# tactileSensorI2c.net
KiCad netlist of a schematic drawn in EAGLE
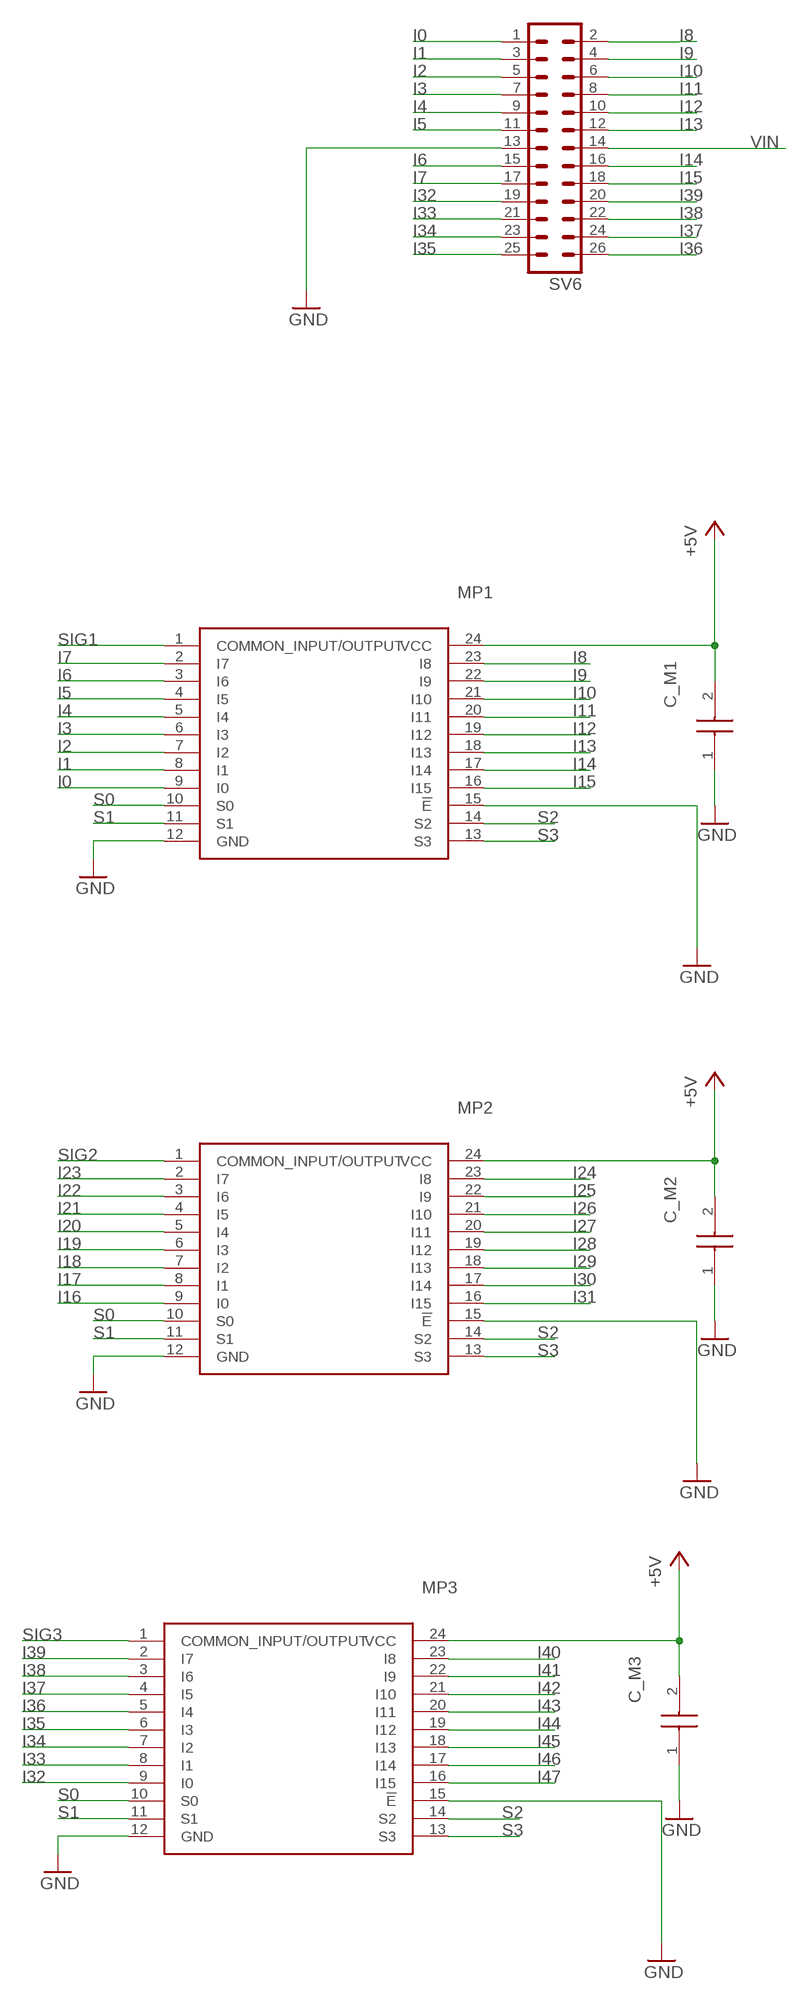
[diagram p0: schematic, sheet 1, part 1 of 2]
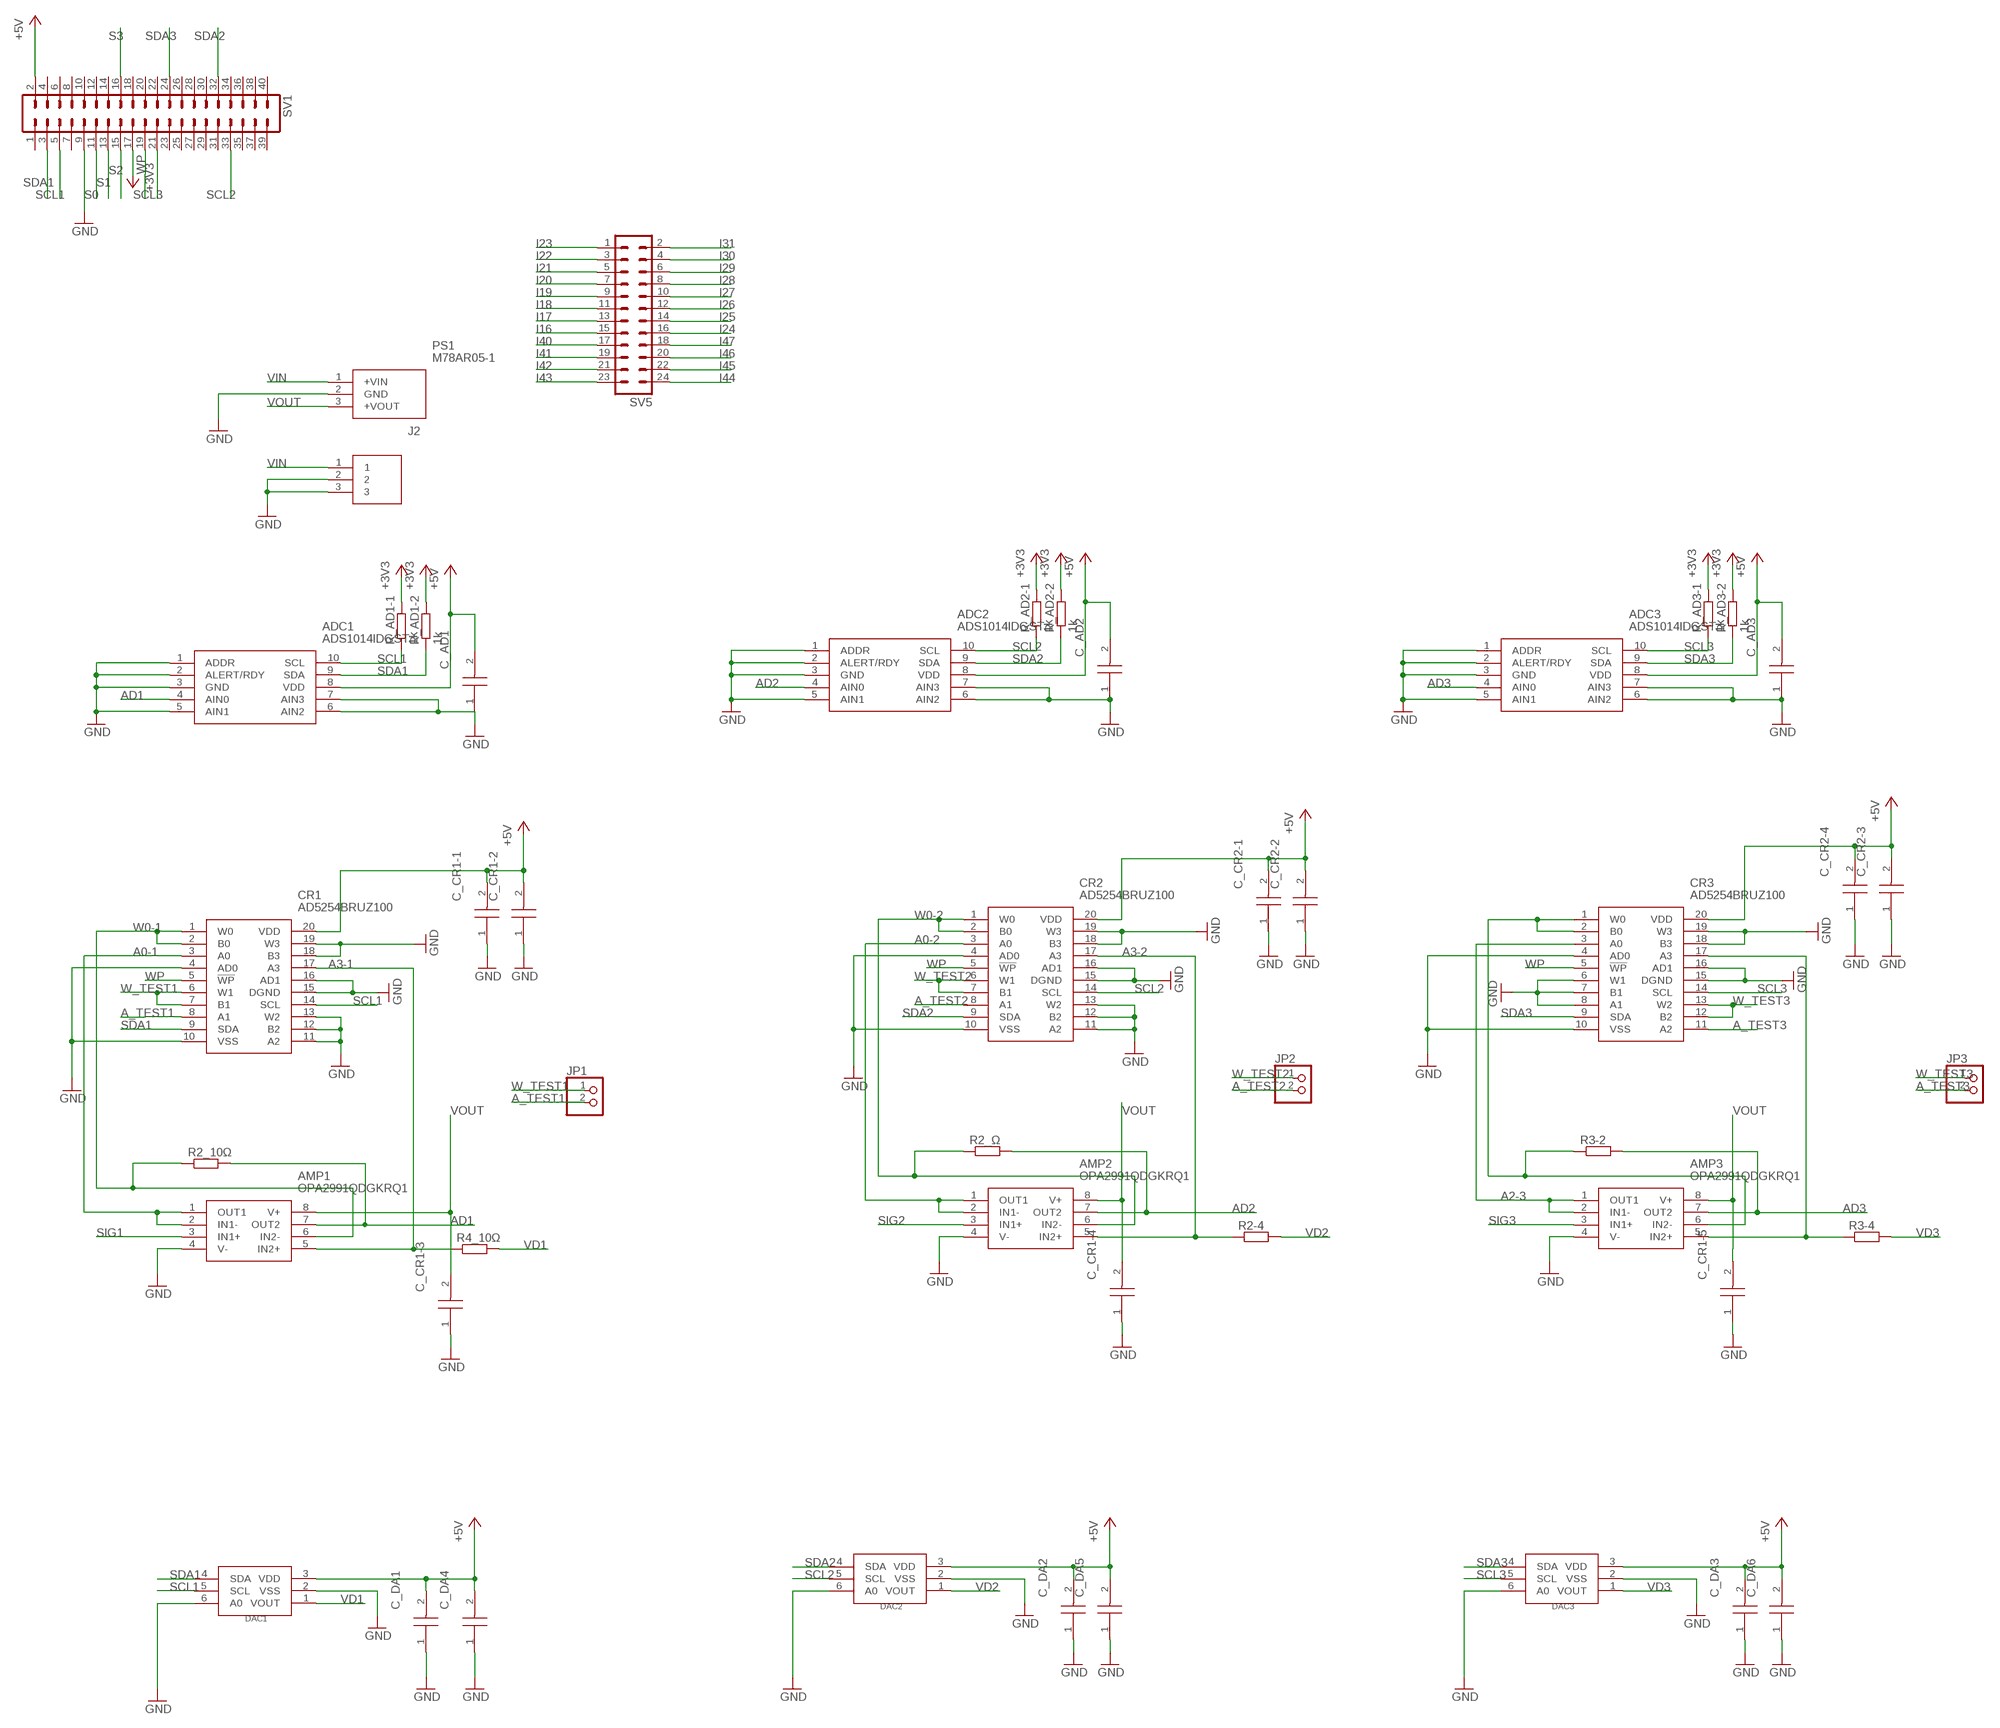
[diagram p1: schematic, sheet 1, part 2 of 2]

(export (version "E")
  (design (tool "Eeschema 10.0.6"))
  (components
    (comp (ref "ADC1")
      (value "ADS1014IDGST")
      (footprint "eagle-import:SOP50P490X110-10N")
      (fields (field (name "RS_PART_NUMBER") "7094557P"))
      (libsource (lib "eagle-import") (part "ADS1014IDGST"))
    )
    (comp (ref "ADC2")
      (value "ADS1014IDGST")
      (footprint "eagle-import:SOP50P490X110-10N")
      (fields (field (name "RS_PART_NUMBER") "7094557P"))
      (libsource (lib "eagle-import") (part "ADS1014IDGST"))
    )
    (comp (ref "ADC3")
      (value "ADS1014IDGST")
      (footprint "eagle-import:SOP50P490X110-10N")
      (fields (field (name "RS_PART_NUMBER") "7094557P"))
      (libsource (lib "eagle-import") (part "ADS1014IDGST"))
    )
    (comp (ref "AMP1")
      (value "OPA2991QDGKRQ1")
      (footprint "eagle-import:SOP65P490X110-8N")
      (libsource (lib "eagle-import") (part "OPA2991QDGKRQ1"))
    )
    (comp (ref "AMP2")
      (value "OPA2991QDGKRQ1")
      (footprint "eagle-import:SOP65P490X110-8N")
      (libsource (lib "eagle-import") (part "OPA2991QDGKRQ1"))
    )
    (comp (ref "AMP3")
      (value "OPA2991QDGKRQ1")
      (footprint "eagle-import:SOP65P490X110-8N")
      (libsource (lib "eagle-import") (part "OPA2991QDGKRQ1"))
    )
    (comp (ref "CR1")
      (value "AD5254BRUZ100")
      (footprint "eagle-import:SOP65P640X120-20N")
      (fields (field (name "RS_PART_NUMBER") "5384858P"))
      (libsource (lib "eagle-import") (part "AD5254BRUZ100"))
    )
    (comp (ref "CR2")
      (value "AD5254BRUZ100")
      (footprint "eagle-import:SOP65P640X120-20N")
      (fields (field (name "RS_PART_NUMBER") "5384858P"))
      (libsource (lib "eagle-import") (part "AD5254BRUZ100"))
    )
    (comp (ref "CR3")
      (value "AD5254BRUZ100")
      (footprint "eagle-import:SOP65P640X120-20N")
      (fields (field (name "RS_PART_NUMBER") "5384858P"))
      (libsource (lib "eagle-import") (part "AD5254BRUZ100"))
    )
    (comp (ref "C_AD1")
      (value "0.1u")
      (footprint "eagle-import:CAPC2012X140N")
      (fields
        (field (name "MANUFACTURER_PART_NUMBER") "C0805C105J3RACTU")
        (field (name "RS_PART_NUMBER") "1464275P")
      )
      (libsource (lib "eagle-import") (part "C0805C105J3RACTU"))
    )
    (comp (ref "C_AD2")
      (value "0.1u")
      (footprint "eagle-import:CAPC2012X140N")
      (fields
        (field (name "MANUFACTURER_PART_NUMBER") "C0805C105J3RACTU")
        (field (name "RS_PART_NUMBER") "1464275P")
      )
      (libsource (lib "eagle-import") (part "C0805C105J3RACTU"))
    )
    (comp (ref "C_AD3")
      (value "0.1u")
      (footprint "eagle-import:CAPC2012X140N")
      (fields
        (field (name "MANUFACTURER_PART_NUMBER") "C0805C105J3RACTU")
        (field (name "RS_PART_NUMBER") "1464275P")
      )
      (libsource (lib "eagle-import") (part "C0805C105J3RACTU"))
    )
    (comp (ref "C_CR1-1")
      (value "0.1u")
      (footprint "eagle-import:CAPC2012X140N")
      (fields
        (field (name "MANUFACTURER_PART_NUMBER") "C0805C105J3RACTU")
        (field (name "RS_PART_NUMBER") "1464275P")
      )
      (libsource (lib "eagle-import") (part "C0805C105J3RACTU"))
    )
    (comp (ref "C_CR1-2")
      (value "10u")
      (footprint "eagle-import:CAPC2012X140N")
      (fields
        (field (name "MANUFACTURER_PART_NUMBER") "C0805C105J3RACTU")
        (field (name "RS_PART_NUMBER") "1464275P")
      )
      (libsource (lib "eagle-import") (part "C0805C105J3RACTU"))
    )
    (comp (ref "C_CR1-3")
      (value "10u")
      (footprint "eagle-import:CAPC2012X140N")
      (fields
        (field (name "MANUFACTURER_PART_NUMBER") "C0805C105J3RACTU")
        (field (name "RS_PART_NUMBER") "1464275P")
      )
      (libsource (lib "eagle-import") (part "C0805C105J3RACTU"))
    )
    (comp (ref "C_CR1-4")
      (value "10u")
      (footprint "eagle-import:CAPC2012X140N")
      (fields
        (field (name "MANUFACTURER_PART_NUMBER") "C0805C105J3RACTU")
        (field (name "RS_PART_NUMBER") "1464275P")
      )
      (libsource (lib "eagle-import") (part "C0805C105J3RACTU"))
    )
    (comp (ref "C_CR1-5")
      (value "10u")
      (footprint "eagle-import:CAPC2012X140N")
      (fields
        (field (name "MANUFACTURER_PART_NUMBER") "C0805C105J3RACTU")
        (field (name "RS_PART_NUMBER") "1464275P")
      )
      (libsource (lib "eagle-import") (part "C0805C105J3RACTU"))
    )
    (comp (ref "C_CR2-1")
      (value "0.1u")
      (footprint "eagle-import:CAPC2012X140N")
      (fields
        (field (name "MANUFACTURER_PART_NUMBER") "C0805C105J3RACTU")
        (field (name "RS_PART_NUMBER") "1464275P")
      )
      (libsource (lib "eagle-import") (part "C0805C105J3RACTU"))
    )
    (comp (ref "C_CR2-2")
      (value "10u")
      (footprint "eagle-import:CAPC2012X140N")
      (fields
        (field (name "MANUFACTURER_PART_NUMBER") "C0805C105J3RACTU")
        (field (name "RS_PART_NUMBER") "1464275P")
      )
      (libsource (lib "eagle-import") (part "C0805C105J3RACTU"))
    )
    (comp (ref "C_CR2-3")
      (value "C0805C105J3RACTU")
      (footprint "eagle-import:CAPC2012X140N")
      (fields (field (name "RS_PART_NUMBER") "1464275P"))
      (libsource (lib "eagle-import") (part "C0805C105J3RACTU"))
    )
    (comp (ref "C_CR2-4")
      (value "C0805C105J3RACTU")
      (footprint "eagle-import:CAPC2012X140N")
      (fields (field (name "RS_PART_NUMBER") "1464275P"))
      (libsource (lib "eagle-import") (part "C0805C105J3RACTU"))
    )
    (comp (ref "C_DA1")
      (value "C0805C105J3RACTU")
      (footprint "eagle-import:CAPC2012X140N")
      (fields (field (name "RS_PART_NUMBER") "1464275P"))
      (libsource (lib "eagle-import") (part "C0805C105J3RACTU"))
    )
    (comp (ref "C_DA2")
      (value "C0805C105J3RACTU")
      (footprint "eagle-import:CAPC2012X140N")
      (fields (field (name "RS_PART_NUMBER") "1464275P"))
      (libsource (lib "eagle-import") (part "C0805C105J3RACTU"))
    )
    (comp (ref "C_DA3")
      (value "C0805C105J3RACTU")
      (footprint "eagle-import:CAPC2012X140N")
      (fields (field (name "RS_PART_NUMBER") "1464275P"))
      (libsource (lib "eagle-import") (part "C0805C105J3RACTU"))
    )
    (comp (ref "C_DA4")
      (value "C0805C105J3RACTU")
      (footprint "eagle-import:CAPC2012X140N")
      (fields (field (name "RS_PART_NUMBER") "1464275P"))
      (libsource (lib "eagle-import") (part "C0805C105J3RACTU"))
    )
    (comp (ref "C_DA5")
      (value "C0805C105J3RACTU")
      (footprint "eagle-import:CAPC2012X140N")
      (fields (field (name "RS_PART_NUMBER") "1464275P"))
      (libsource (lib "eagle-import") (part "C0805C105J3RACTU"))
    )
    (comp (ref "C_DA6")
      (value "C0805C105J3RACTU")
      (footprint "eagle-import:CAPC2012X140N")
      (fields (field (name "RS_PART_NUMBER") "1464275P"))
      (libsource (lib "eagle-import") (part "C0805C105J3RACTU"))
    )
    (comp (ref "C_M1")
      (value "0.1u")
      (footprint "eagle-import:CAPC2012X140N")
      (fields
        (field (name "MANUFACTURER_PART_NUMBER") "C0805C105J3RACTU")
        (field (name "RS_PART_NUMBER") "1464275P")
      )
      (libsource (lib "eagle-import") (part "C0805C105J3RACTU"))
    )
    (comp (ref "C_M2")
      (value "0.1u")
      (footprint "eagle-import:CAPC2012X140N")
      (fields
        (field (name "MANUFACTURER_PART_NUMBER") "C0805C105J3RACTU")
        (field (name "RS_PART_NUMBER") "1464275P")
      )
      (libsource (lib "eagle-import") (part "C0805C105J3RACTU"))
    )
    (comp (ref "C_M3")
      (value "0.1u")
      (footprint "eagle-import:CAPC2012X140N")
      (fields
        (field (name "MANUFACTURER_PART_NUMBER") "C0805C105J3RACTU")
        (field (name "RS_PART_NUMBER") "1464275P")
      )
      (libsource (lib "eagle-import") (part "C0805C105J3RACTU"))
    )
    (comp (ref "DAC1")
      (value "MCP4725")
      (footprint "eagle-import:SOT23-6")
      (libsource (lib "eagle-import") (part "MCP4725"))
    )
    (comp (ref "DAC2")
      (value "MCP4725")
      (footprint "eagle-import:SOT23-6")
      (libsource (lib "eagle-import") (part "MCP4725"))
    )
    (comp (ref "DAC3")
      (value "MCP4725")
      (footprint "eagle-import:SOT23-6")
      (libsource (lib "eagle-import") (part "MCP4725"))
    )
    (comp (ref "J2")
      (value "1725669")
      (footprint "eagle-import:1725669")
      (fields (field (name "MOUSER_PART_NUMBER") "651-1725669"))
      (libsource (lib "eagle-import") (part "1725669"))
    )
    (comp (ref "JP1")
      (value "PINHD-1X2")
      (footprint "eagle-import:1X02")
      (libsource (lib "eagle-import") (part "PINHD-1X2"))
    )
    (comp (ref "JP2")
      (value "PINHD-1X2")
      (footprint "eagle-import:1X02")
      (libsource (lib "eagle-import") (part "PINHD-1X2"))
    )
    (comp (ref "JP3")
      (value "PINHD-1X2")
      (footprint "eagle-import:1X02")
      (libsource (lib "eagle-import") (part "PINHD-1X2"))
    )
    (comp (ref "MP1")
      (value "CD74HC4067SM96")
      (footprint "eagle-import:SOP65P780X200-24N")
      (fields (field (name "MOUSER_PART_NUMBER") "595-CD74HC4067SM96"))
      (libsource (lib "eagle-import") (part "CD74HC4067SM96"))
    )
    (comp (ref "MP2")
      (value "CD74HC4067SM96")
      (footprint "eagle-import:SOP65P780X200-24N")
      (fields (field (name "MOUSER_PART_NUMBER") "595-CD74HC4067SM96"))
      (libsource (lib "eagle-import") (part "CD74HC4067SM96"))
    )
    (comp (ref "MP3")
      (value "CD74HC4067SM96")
      (footprint "eagle-import:SOP65P780X200-24N")
      (fields (field (name "MOUSER_PART_NUMBER") "595-CD74HC4067SM96"))
      (libsource (lib "eagle-import") (part "CD74HC4067SM96"))
    )
    (comp (ref "PS1")
      (value "M78AR05-1")
      (footprint "eagle-import:M78AR05")
      (libsource (lib "eagle-import") (part "M78AR05-1"))
    )
    (comp (ref "R2-4")
      (value "R-EU_0204/2V")
      (footprint "eagle-import:0204V")
      (libsource (lib "eagle-import") (part "R-EU_0204/2V"))
    )
    (comp (ref "R2_10Ω")
      (value "R-EU_0204/2V")
      (footprint "eagle-import:0204V")
      (libsource (lib "eagle-import") (part "R-EU_0204/2V"))
    )
    (comp (ref "R2_Ω")
      (value "R-EU_0204/2V")
      (footprint "eagle-import:0204V")
      (libsource (lib "eagle-import") (part "R-EU_0204/2V"))
    )
    (comp (ref "R3-2")
      (value "R-EU_0204/2V")
      (footprint "eagle-import:0204V")
      (libsource (lib "eagle-import") (part "R-EU_0204/2V"))
    )
    (comp (ref "R3-4")
      (value "R-EU_0204/2V")
      (footprint "eagle-import:0204V")
      (libsource (lib "eagle-import") (part "R-EU_0204/2V"))
    )
    (comp (ref "R4_10Ω")
      (value "R-EU_0204/2V")
      (footprint "eagle-import:0204V")
      (libsource (lib "eagle-import") (part "R-EU_0204/2V"))
    )
    (comp (ref "R_AD1-1")
      (value "1k")
      (footprint "eagle-import:R0805")
      (libsource (lib "eagle-import") (part "R-EU_R0805"))
    )
    (comp (ref "R_AD1-2")
      (value "1k")
      (footprint "eagle-import:R0805")
      (libsource (lib "eagle-import") (part "R-EU_R0805"))
    )
    (comp (ref "R_AD2-1")
      (value "1k")
      (footprint "eagle-import:R0805")
      (libsource (lib "eagle-import") (part "R-EU_R0805"))
    )
    (comp (ref "R_AD2-2")
      (value "1k")
      (footprint "eagle-import:R0805")
      (libsource (lib "eagle-import") (part "R-EU_R0805"))
    )
    (comp (ref "R_AD3-1")
      (value "1k")
      (footprint "eagle-import:R0805")
      (libsource (lib "eagle-import") (part "R-EU_R0805"))
    )
    (comp (ref "R_AD3-2")
      (value "1k")
      (footprint "eagle-import:R0805")
      (libsource (lib "eagle-import") (part "R-EU_R0805"))
    )
    (comp (ref "SV1")
      (value "MA20-2")
      (footprint "eagle-import:MA20-2")
      (libsource (lib "eagle-import") (part "MA20-2"))
    )
    (comp (ref "SV5")
      (value "MA12-2")
      (footprint "eagle-import:MA12-2")
      (libsource (lib "eagle-import") (part "MA12-2"))
    )
    (comp (ref "SV6")
      (value "MA13-2")
      (footprint "eagle-import:MA13-2")
      (libsource (lib "eagle-import") (part "MA13-2"))
    )
  )
  (nets
    (net (code "1") (name "+3V3") (class "Default")
      (node (ref "R_AD1-1") (pin "2") (pinfunction "2_2") (pintype "passive"))
      (node (ref "R_AD1-2") (pin "2") (pinfunction "2_2") (pintype "passive"))
      (node (ref "R_AD2-1") (pin "2") (pinfunction "2_2") (pintype "passive"))
      (node (ref "R_AD2-2") (pin "2") (pinfunction "2_2") (pintype "passive"))
      (node (ref "R_AD3-1") (pin "2") (pinfunction "2_2") (pintype "passive"))
      (node (ref "R_AD3-2") (pin "2") (pinfunction "2_2") (pintype "passive"))
      (node (ref "SV1") (pin "17") (pinfunction "17_17") (pintype "passive"))
    )
    (net (code "2") (name "+5V") (class "Default")
      (node (ref "ADC1") (pin "8") (pinfunction "VDD_8") (pintype "bidirectional"))
      (node (ref "ADC2") (pin "8") (pinfunction "VDD_8") (pintype "bidirectional"))
      (node (ref "ADC3") (pin "8") (pinfunction "VDD_8") (pintype "bidirectional"))
      (node (ref "CR1") (pin "20") (pinfunction "VDD_20") (pintype "bidirectional"))
      (node (ref "CR2") (pin "20") (pinfunction "VDD_20") (pintype "bidirectional"))
      (node (ref "CR3") (pin "20") (pinfunction "VDD_20") (pintype "bidirectional"))
      (node (ref "C_AD1") (pin "2") (pinfunction "2_2") (pintype "bidirectional"))
      (node (ref "C_AD2") (pin "2") (pinfunction "2_2") (pintype "bidirectional"))
      (node (ref "C_AD3") (pin "2") (pinfunction "2_2") (pintype "bidirectional"))
      (node (ref "C_CR1-1") (pin "2") (pinfunction "2_2") (pintype "bidirectional"))
      (node (ref "C_CR1-2") (pin "2") (pinfunction "2_2") (pintype "bidirectional"))
      (node (ref "C_CR2-1") (pin "2") (pinfunction "2_2") (pintype "bidirectional"))
      (node (ref "C_CR2-2") (pin "2") (pinfunction "2_2") (pintype "bidirectional"))
      (node (ref "C_CR2-3") (pin "2") (pinfunction "2_2") (pintype "bidirectional"))
      (node (ref "C_CR2-4") (pin "2") (pinfunction "2_2") (pintype "bidirectional"))
      (node (ref "C_DA1") (pin "2") (pinfunction "2_2") (pintype "bidirectional"))
      (node (ref "C_DA2") (pin "2") (pinfunction "2_2") (pintype "bidirectional"))
      (node (ref "C_DA3") (pin "2") (pinfunction "2_2") (pintype "bidirectional"))
      (node (ref "C_DA4") (pin "2") (pinfunction "2_2") (pintype "bidirectional"))
      (node (ref "C_DA5") (pin "2") (pinfunction "2_2") (pintype "bidirectional"))
      (node (ref "C_DA6") (pin "2") (pinfunction "2_2") (pintype "bidirectional"))
      (node (ref "C_M1") (pin "2") (pinfunction "2_2") (pintype "bidirectional"))
      (node (ref "C_M2") (pin "2") (pinfunction "2_2") (pintype "bidirectional"))
      (node (ref "C_M3") (pin "2") (pinfunction "2_2") (pintype "bidirectional"))
      (node (ref "DAC1") (pin "3") (pinfunction "VDD_3") (pintype "bidirectional"))
      (node (ref "DAC2") (pin "3") (pinfunction "VDD_3") (pintype "bidirectional"))
      (node (ref "DAC3") (pin "3") (pinfunction "VDD_3") (pintype "bidirectional"))
      (node (ref "MP1") (pin "24") (pinfunction "VCC_24") (pintype "bidirectional"))
      (node (ref "MP2") (pin "24") (pinfunction "VCC_24") (pintype "bidirectional"))
      (node (ref "MP3") (pin "24") (pinfunction "VCC_24") (pintype "bidirectional"))
      (node (ref "SV1") (pin "2") (pinfunction "2_2") (pintype "passive"))
    )
    (net (code "3") (name "/A0-1") (class "Default")
      (node (ref "AMP1") (pin "1") (pinfunction "OUT1_1") (pintype "bidirectional"))
      (node (ref "AMP1") (pin "2") (pinfunction "IN1-_2") (pintype "bidirectional"))
      (node (ref "CR1") (pin "3") (pinfunction "A0_3") (pintype "bidirectional"))
    )
    (net (code "4") (name "/A0-2") (class "Default")
      (node (ref "AMP2") (pin "1") (pinfunction "OUT1_1") (pintype "bidirectional"))
      (node (ref "AMP2") (pin "2") (pinfunction "IN1-_2") (pintype "bidirectional"))
      (node (ref "CR2") (pin "3") (pinfunction "A0_3") (pintype "bidirectional"))
    )
    (net (code "5") (name "/A2-3") (class "Default")
      (node (ref "AMP3") (pin "1") (pinfunction "OUT1_1") (pintype "bidirectional"))
      (node (ref "AMP3") (pin "2") (pinfunction "IN1-_2") (pintype "bidirectional"))
      (node (ref "CR3") (pin "3") (pinfunction "A0_3") (pintype "bidirectional"))
    )
    (net (code "6") (name "/A3-1") (class "Default")
      (node (ref "AMP1") (pin "5") (pinfunction "IN2+_5") (pintype "bidirectional"))
      (node (ref "CR1") (pin "17") (pinfunction "A3_17") (pintype "bidirectional"))
      (node (ref "R4_10Ω") (pin "1") (pinfunction "1_1") (pintype "passive"))
    )
    (net (code "7") (name "/A3-2") (class "Default")
      (node (ref "AMP2") (pin "5") (pinfunction "IN2+_5") (pintype "bidirectional"))
      (node (ref "CR2") (pin "17") (pinfunction "A3_17") (pintype "bidirectional"))
      (node (ref "R2-4") (pin "1") (pinfunction "1_1") (pintype "passive"))
    )
    (net (code "8") (name "/AD1") (class "Default")
      (node (ref "ADC1") (pin "4") (pinfunction "AIN0_4") (pintype "bidirectional"))
      (node (ref "AMP1") (pin "7") (pinfunction "OUT2_7") (pintype "bidirectional"))
      (node (ref "R2_10Ω") (pin "2") (pinfunction "2_2") (pintype "passive"))
    )
    (net (code "9") (name "/AD2") (class "Default")
      (node (ref "ADC2") (pin "4") (pinfunction "AIN0_4") (pintype "bidirectional"))
      (node (ref "AMP2") (pin "7") (pinfunction "OUT2_7") (pintype "bidirectional"))
      (node (ref "R2_Ω") (pin "2") (pinfunction "2_2") (pintype "passive"))
    )
    (net (code "10") (name "/AD3") (class "Default")
      (node (ref "ADC3") (pin "4") (pinfunction "AIN0_4") (pintype "bidirectional"))
      (node (ref "AMP3") (pin "7") (pinfunction "OUT2_7") (pintype "bidirectional"))
      (node (ref "R3-2") (pin "2") (pinfunction "2_2") (pintype "passive"))
    )
    (net (code "11") (name "/A_TEST1") (class "Default")
      (node (ref "CR1") (pin "8") (pinfunction "A1_8") (pintype "bidirectional"))
      (node (ref "JP1") (pin "2") (pinfunction "2_2") (pintype "passive"))
    )
    (net (code "12") (name "/A_TEST2") (class "Default")
      (node (ref "CR2") (pin "8") (pinfunction "A1_8") (pintype "bidirectional"))
      (node (ref "JP2") (pin "2") (pinfunction "2_2") (pintype "passive"))
    )
    (net (code "13") (name "/A_TEST3") (class "Default")
      (node (ref "CR3") (pin "11") (pinfunction "A2_11") (pintype "bidirectional"))
      (node (ref "JP3") (pin "2") (pinfunction "2_2") (pintype "passive"))
    )
    (net (code "14") (name "/I0") (class "Default")
      (node (ref "MP1") (pin "9") (pinfunction "I0_9") (pintype "bidirectional"))
      (node (ref "SV6") (pin "1") (pinfunction "1_1") (pintype "passive"))
    )
    (net (code "15") (name "/I1") (class "Default")
      (node (ref "MP1") (pin "8") (pinfunction "I1_8") (pintype "bidirectional"))
      (node (ref "SV6") (pin "3") (pinfunction "3_3") (pintype "passive"))
    )
    (net (code "16") (name "/I2") (class "Default")
      (node (ref "MP1") (pin "7") (pinfunction "I2_7") (pintype "bidirectional"))
      (node (ref "SV6") (pin "5") (pinfunction "5_5") (pintype "passive"))
    )
    (net (code "17") (name "/I3") (class "Default")
      (node (ref "MP1") (pin "6") (pinfunction "I3_6") (pintype "bidirectional"))
      (node (ref "SV6") (pin "7") (pinfunction "7_7") (pintype "passive"))
    )
    (net (code "18") (name "/I4") (class "Default")
      (node (ref "MP1") (pin "5") (pinfunction "I4_5") (pintype "bidirectional"))
      (node (ref "SV6") (pin "9") (pinfunction "9_9") (pintype "passive"))
    )
    (net (code "19") (name "/I5") (class "Default")
      (node (ref "MP1") (pin "4") (pinfunction "I5_4") (pintype "bidirectional"))
      (node (ref "SV6") (pin "11") (pinfunction "11_11") (pintype "passive"))
    )
    (net (code "20") (name "/I6") (class "Default")
      (node (ref "MP1") (pin "3") (pinfunction "I6_3") (pintype "bidirectional"))
      (node (ref "SV6") (pin "15") (pinfunction "15_15") (pintype "passive"))
    )
    (net (code "21") (name "/I7") (class "Default")
      (node (ref "MP1") (pin "2") (pinfunction "I7_2") (pintype "bidirectional"))
      (node (ref "SV6") (pin "17") (pinfunction "17_17") (pintype "passive"))
    )
    (net (code "22") (name "/I8") (class "Default")
      (node (ref "MP1") (pin "23") (pinfunction "I8_23") (pintype "bidirectional"))
      (node (ref "SV6") (pin "2") (pinfunction "2_2") (pintype "passive"))
    )
    (net (code "23") (name "/I9") (class "Default")
      (node (ref "MP1") (pin "22") (pinfunction "I9_22") (pintype "bidirectional"))
      (node (ref "SV6") (pin "4") (pinfunction "4_4") (pintype "passive"))
    )
    (net (code "24") (name "/I10") (class "Default")
      (node (ref "MP1") (pin "21") (pinfunction "I10_21") (pintype "bidirectional"))
      (node (ref "SV6") (pin "6") (pinfunction "6_6") (pintype "passive"))
    )
    (net (code "25") (name "/I11") (class "Default")
      (node (ref "MP1") (pin "20") (pinfunction "I11_20") (pintype "bidirectional"))
      (node (ref "SV6") (pin "8") (pinfunction "8_8") (pintype "passive"))
    )
    (net (code "26") (name "/I12") (class "Default")
      (node (ref "MP1") (pin "19") (pinfunction "I12_19") (pintype "bidirectional"))
      (node (ref "SV6") (pin "10") (pinfunction "10_10") (pintype "passive"))
    )
    (net (code "27") (name "/I13") (class "Default")
      (node (ref "MP1") (pin "18") (pinfunction "I13_18") (pintype "bidirectional"))
      (node (ref "SV6") (pin "12") (pinfunction "12_12") (pintype "passive"))
    )
    (net (code "28") (name "/I14") (class "Default")
      (node (ref "MP1") (pin "17") (pinfunction "I14_17") (pintype "bidirectional"))
      (node (ref "SV6") (pin "16") (pinfunction "16_16") (pintype "passive"))
    )
    (net (code "29") (name "/I15") (class "Default")
      (node (ref "MP1") (pin "16") (pinfunction "I15_16") (pintype "bidirectional"))
      (node (ref "SV6") (pin "18") (pinfunction "18_18") (pintype "passive"))
    )
    (net (code "30") (name "/I16") (class "Default")
      (node (ref "MP2") (pin "9") (pinfunction "I0_9") (pintype "bidirectional"))
      (node (ref "SV5") (pin "15") (pinfunction "15_15") (pintype "passive"))
    )
    (net (code "31") (name "/I17") (class "Default")
      (node (ref "MP2") (pin "8") (pinfunction "I1_8") (pintype "bidirectional"))
      (node (ref "SV5") (pin "13") (pinfunction "13_13") (pintype "passive"))
    )
    (net (code "32") (name "/I18") (class "Default")
      (node (ref "MP2") (pin "7") (pinfunction "I2_7") (pintype "bidirectional"))
      (node (ref "SV5") (pin "11") (pinfunction "11_11") (pintype "passive"))
    )
    (net (code "33") (name "/I19") (class "Default")
      (node (ref "MP2") (pin "6") (pinfunction "I3_6") (pintype "bidirectional"))
      (node (ref "SV5") (pin "9") (pinfunction "9_9") (pintype "passive"))
    )
    (net (code "34") (name "/I20") (class "Default")
      (node (ref "MP2") (pin "5") (pinfunction "I4_5") (pintype "bidirectional"))
      (node (ref "SV5") (pin "7") (pinfunction "7_7") (pintype "passive"))
    )
    (net (code "35") (name "/I21") (class "Default")
      (node (ref "MP2") (pin "4") (pinfunction "I5_4") (pintype "bidirectional"))
      (node (ref "SV5") (pin "5") (pinfunction "5_5") (pintype "passive"))
    )
    (net (code "36") (name "/I22") (class "Default")
      (node (ref "MP2") (pin "3") (pinfunction "I6_3") (pintype "bidirectional"))
      (node (ref "SV5") (pin "3") (pinfunction "3_3") (pintype "passive"))
    )
    (net (code "37") (name "/I23") (class "Default")
      (node (ref "MP2") (pin "2") (pinfunction "I7_2") (pintype "bidirectional"))
      (node (ref "SV5") (pin "1") (pinfunction "1_1") (pintype "passive"))
    )
    (net (code "38") (name "/I24") (class "Default")
      (node (ref "MP2") (pin "23") (pinfunction "I8_23") (pintype "bidirectional"))
      (node (ref "SV5") (pin "16") (pinfunction "16_16") (pintype "passive"))
    )
    (net (code "39") (name "/I25") (class "Default")
      (node (ref "MP2") (pin "22") (pinfunction "I9_22") (pintype "bidirectional"))
      (node (ref "SV5") (pin "14") (pinfunction "14_14") (pintype "passive"))
    )
    (net (code "40") (name "/I26") (class "Default")
      (node (ref "MP2") (pin "21") (pinfunction "I10_21") (pintype "bidirectional"))
      (node (ref "SV5") (pin "12") (pinfunction "12_12") (pintype "passive"))
    )
    (net (code "41") (name "/I27") (class "Default")
      (node (ref "MP2") (pin "20") (pinfunction "I11_20") (pintype "bidirectional"))
      (node (ref "SV5") (pin "10") (pinfunction "10_10") (pintype "passive"))
    )
    (net (code "42") (name "/I28") (class "Default")
      (node (ref "MP2") (pin "19") (pinfunction "I12_19") (pintype "bidirectional"))
      (node (ref "SV5") (pin "8") (pinfunction "8_8") (pintype "passive"))
    )
    (net (code "43") (name "/I29") (class "Default")
      (node (ref "MP2") (pin "18") (pinfunction "I13_18") (pintype "bidirectional"))
      (node (ref "SV5") (pin "6") (pinfunction "6_6") (pintype "passive"))
    )
    (net (code "44") (name "/I30") (class "Default")
      (node (ref "MP2") (pin "17") (pinfunction "I14_17") (pintype "bidirectional"))
      (node (ref "SV5") (pin "4") (pinfunction "4_4") (pintype "passive"))
    )
    (net (code "45") (name "/I31") (class "Default")
      (node (ref "MP2") (pin "16") (pinfunction "I15_16") (pintype "bidirectional"))
      (node (ref "SV5") (pin "2") (pinfunction "2_2") (pintype "passive"))
    )
    (net (code "46") (name "/I32") (class "Default")
      (node (ref "MP3") (pin "9") (pinfunction "I0_9") (pintype "bidirectional"))
      (node (ref "SV6") (pin "19") (pinfunction "19_19") (pintype "passive"))
    )
    (net (code "47") (name "/I33") (class "Default")
      (node (ref "MP3") (pin "8") (pinfunction "I1_8") (pintype "bidirectional"))
      (node (ref "SV6") (pin "21") (pinfunction "21_21") (pintype "passive"))
    )
    (net (code "48") (name "/I34") (class "Default")
      (node (ref "MP3") (pin "7") (pinfunction "I2_7") (pintype "bidirectional"))
      (node (ref "SV6") (pin "23") (pinfunction "23_23") (pintype "passive"))
    )
    (net (code "49") (name "/I35") (class "Default")
      (node (ref "MP3") (pin "6") (pinfunction "I3_6") (pintype "bidirectional"))
      (node (ref "SV6") (pin "25") (pinfunction "25_25") (pintype "passive"))
    )
    (net (code "50") (name "/I36") (class "Default")
      (node (ref "MP3") (pin "5") (pinfunction "I4_5") (pintype "bidirectional"))
      (node (ref "SV6") (pin "26") (pinfunction "26_26") (pintype "passive"))
    )
    (net (code "51") (name "/I37") (class "Default")
      (node (ref "MP3") (pin "4") (pinfunction "I5_4") (pintype "bidirectional"))
      (node (ref "SV6") (pin "24") (pinfunction "24_24") (pintype "passive"))
    )
    (net (code "52") (name "/I38") (class "Default")
      (node (ref "MP3") (pin "3") (pinfunction "I6_3") (pintype "bidirectional"))
      (node (ref "SV6") (pin "22") (pinfunction "22_22") (pintype "passive"))
    )
    (net (code "53") (name "/I39") (class "Default")
      (node (ref "MP3") (pin "2") (pinfunction "I7_2") (pintype "bidirectional"))
      (node (ref "SV6") (pin "20") (pinfunction "20_20") (pintype "passive"))
    )
    (net (code "54") (name "/I40") (class "Default")
      (node (ref "MP3") (pin "23") (pinfunction "I8_23") (pintype "bidirectional"))
      (node (ref "SV5") (pin "17") (pinfunction "17_17") (pintype "passive"))
    )
    (net (code "55") (name "/I41") (class "Default")
      (node (ref "MP3") (pin "22") (pinfunction "I9_22") (pintype "bidirectional"))
      (node (ref "SV5") (pin "19") (pinfunction "19_19") (pintype "passive"))
    )
    (net (code "56") (name "/I42") (class "Default")
      (node (ref "MP3") (pin "21") (pinfunction "I10_21") (pintype "bidirectional"))
      (node (ref "SV5") (pin "21") (pinfunction "21_21") (pintype "passive"))
    )
    (net (code "57") (name "/I43") (class "Default")
      (node (ref "MP3") (pin "20") (pinfunction "I11_20") (pintype "bidirectional"))
      (node (ref "SV5") (pin "23") (pinfunction "23_23") (pintype "passive"))
    )
    (net (code "58") (name "/I44") (class "Default")
      (node (ref "MP3") (pin "19") (pinfunction "I12_19") (pintype "bidirectional"))
      (node (ref "SV5") (pin "24") (pinfunction "24_24") (pintype "passive"))
    )
    (net (code "59") (name "/I45") (class "Default")
      (node (ref "MP3") (pin "18") (pinfunction "I13_18") (pintype "bidirectional"))
      (node (ref "SV5") (pin "22") (pinfunction "22_22") (pintype "passive"))
    )
    (net (code "60") (name "/I46") (class "Default")
      (node (ref "MP3") (pin "17") (pinfunction "I14_17") (pintype "bidirectional"))
      (node (ref "SV5") (pin "20") (pinfunction "20_20") (pintype "passive"))
    )
    (net (code "61") (name "/I47") (class "Default")
      (node (ref "MP3") (pin "16") (pinfunction "I15_16") (pintype "bidirectional"))
      (node (ref "SV5") (pin "18") (pinfunction "18_18") (pintype "passive"))
    )
    (net (code "62") (name "/S0") (class "Default")
      (node (ref "MP1") (pin "10") (pinfunction "S0_10") (pintype "bidirectional"))
      (node (ref "MP2") (pin "10") (pinfunction "S0_10") (pintype "bidirectional"))
      (node (ref "MP3") (pin "10") (pinfunction "S0_10") (pintype "bidirectional"))
      (node (ref "SV1") (pin "11") (pinfunction "11_11") (pintype "passive"))
    )
    (net (code "63") (name "/S1") (class "Default")
      (node (ref "MP1") (pin "11") (pinfunction "S1_11") (pintype "bidirectional"))
      (node (ref "MP2") (pin "11") (pinfunction "S1_11") (pintype "bidirectional"))
      (node (ref "MP3") (pin "11") (pinfunction "S1_11") (pintype "bidirectional"))
      (node (ref "SV1") (pin "13") (pinfunction "13_13") (pintype "passive"))
    )
    (net (code "64") (name "/S2") (class "Default")
      (node (ref "MP1") (pin "14") (pinfunction "S2_14") (pintype "bidirectional"))
      (node (ref "MP2") (pin "14") (pinfunction "S2_14") (pintype "bidirectional"))
      (node (ref "MP3") (pin "14") (pinfunction "S2_14") (pintype "bidirectional"))
      (node (ref "SV1") (pin "15") (pinfunction "15_15") (pintype "passive"))
    )
    (net (code "65") (name "/S3") (class "Default")
      (node (ref "MP1") (pin "13") (pinfunction "S3_13") (pintype "bidirectional"))
      (node (ref "MP2") (pin "13") (pinfunction "S3_13") (pintype "bidirectional"))
      (node (ref "MP3") (pin "13") (pinfunction "S3_13") (pintype "bidirectional"))
      (node (ref "SV1") (pin "16") (pinfunction "16_16") (pintype "passive"))
    )
    (net (code "66") (name "/SCL1") (class "Default")
      (node (ref "ADC1") (pin "10") (pinfunction "SCL_10") (pintype "bidirectional"))
      (node (ref "CR1") (pin "14") (pinfunction "SCL_14") (pintype "bidirectional"))
      (node (ref "DAC1") (pin "5") (pinfunction "SCL_5") (pintype "bidirectional"))
      (node (ref "R_AD1-1") (pin "1") (pinfunction "1_1") (pintype "passive"))
      (node (ref "SV1") (pin "5") (pinfunction "5_5") (pintype "passive"))
    )
    (net (code "67") (name "/SCL2") (class "Default")
      (node (ref "ADC2") (pin "10") (pinfunction "SCL_10") (pintype "bidirectional"))
      (node (ref "CR2") (pin "14") (pinfunction "SCL_14") (pintype "bidirectional"))
      (node (ref "DAC2") (pin "5") (pinfunction "SCL_5") (pintype "bidirectional"))
      (node (ref "R_AD2-1") (pin "1") (pinfunction "1_1") (pintype "passive"))
      (node (ref "SV1") (pin "33") (pinfunction "33_33") (pintype "passive"))
    )
    (net (code "68") (name "/SCL3") (class "Default")
      (node (ref "ADC3") (pin "10") (pinfunction "SCL_10") (pintype "bidirectional"))
      (node (ref "CR3") (pin "14") (pinfunction "SCL_14") (pintype "bidirectional"))
      (node (ref "DAC3") (pin "5") (pinfunction "SCL_5") (pintype "bidirectional"))
      (node (ref "R_AD3-1") (pin "1") (pinfunction "1_1") (pintype "passive"))
      (node (ref "SV1") (pin "21") (pinfunction "21_21") (pintype "passive"))
    )
    (net (code "69") (name "/SDA1") (class "Default")
      (node (ref "ADC1") (pin "9") (pinfunction "SDA_9") (pintype "bidirectional"))
      (node (ref "CR1") (pin "9") (pinfunction "SDA_9") (pintype "bidirectional"))
      (node (ref "DAC1") (pin "4") (pinfunction "SDA_4") (pintype "bidirectional"))
      (node (ref "R_AD1-2") (pin "1") (pinfunction "1_1") (pintype "passive"))
      (node (ref "SV1") (pin "3") (pinfunction "3_3") (pintype "passive"))
    )
    (net (code "70") (name "/SDA2") (class "Default")
      (node (ref "ADC2") (pin "9") (pinfunction "SDA_9") (pintype "bidirectional"))
      (node (ref "CR2") (pin "9") (pinfunction "SDA_9") (pintype "bidirectional"))
      (node (ref "DAC2") (pin "4") (pinfunction "SDA_4") (pintype "bidirectional"))
      (node (ref "R_AD2-2") (pin "1") (pinfunction "1_1") (pintype "passive"))
      (node (ref "SV1") (pin "32") (pinfunction "32_32") (pintype "passive"))
    )
    (net (code "71") (name "/SDA3") (class "Default")
      (node (ref "ADC3") (pin "9") (pinfunction "SDA_9") (pintype "bidirectional"))
      (node (ref "CR3") (pin "9") (pinfunction "SDA_9") (pintype "bidirectional"))
      (node (ref "DAC3") (pin "4") (pinfunction "SDA_4") (pintype "bidirectional"))
      (node (ref "R_AD3-2") (pin "1") (pinfunction "1_1") (pintype "passive"))
      (node (ref "SV1") (pin "24") (pinfunction "24_24") (pintype "passive"))
    )
    (net (code "72") (name "/SIG1") (class "Default")
      (node (ref "AMP1") (pin "3") (pinfunction "IN1+_3") (pintype "bidirectional"))
      (node (ref "MP1") (pin "1") (pinfunction "COMMON_INPUT/OUTPUT_1") (pintype "bidirectional"))
    )
    (net (code "73") (name "/SIG2") (class "Default")
      (node (ref "AMP2") (pin "3") (pinfunction "IN1+_3") (pintype "bidirectional"))
      (node (ref "MP2") (pin "1") (pinfunction "COMMON_INPUT/OUTPUT_1") (pintype "bidirectional"))
    )
    (net (code "74") (name "/SIG3") (class "Default")
      (node (ref "AMP3") (pin "3") (pinfunction "IN1+_3") (pintype "bidirectional"))
      (node (ref "MP3") (pin "1") (pinfunction "COMMON_INPUT/OUTPUT_1") (pintype "bidirectional"))
    )
    (net (code "75") (name "/VD1") (class "Default")
      (node (ref "DAC1") (pin "1") (pinfunction "VOUT_1") (pintype "bidirectional"))
      (node (ref "R4_10Ω") (pin "2") (pinfunction "2_2") (pintype "passive"))
    )
    (net (code "76") (name "/VD2") (class "Default")
      (node (ref "DAC2") (pin "1") (pinfunction "VOUT_1") (pintype "bidirectional"))
      (node (ref "R2-4") (pin "2") (pinfunction "2_2") (pintype "passive"))
    )
    (net (code "77") (name "/VD3") (class "Default")
      (node (ref "DAC3") (pin "1") (pinfunction "VOUT_1") (pintype "bidirectional"))
      (node (ref "R3-4") (pin "2") (pinfunction "2_2") (pintype "passive"))
    )
    (net (code "78") (name "/VIN") (class "Default")
      (node (ref "J2") (pin "1") (pinfunction "1_1") (pintype "bidirectional"))
      (node (ref "PS1") (pin "1") (pinfunction "+VIN_1") (pintype "bidirectional"))
      (node (ref "SV6") (pin "14") (pinfunction "14_14") (pintype "passive"))
    )
    (net (code "79") (name "/VOUT") (class "Default")
      (node (ref "AMP1") (pin "8") (pinfunction "V+_8") (pintype "bidirectional"))
      (node (ref "AMP2") (pin "8") (pinfunction "V+_8") (pintype "bidirectional"))
      (node (ref "AMP3") (pin "8") (pinfunction "V+_8") (pintype "bidirectional"))
      (node (ref "C_CR1-3") (pin "2") (pinfunction "2_2") (pintype "bidirectional"))
      (node (ref "C_CR1-4") (pin "2") (pinfunction "2_2") (pintype "bidirectional"))
      (node (ref "C_CR1-5") (pin "2") (pinfunction "2_2") (pintype "bidirectional"))
      (node (ref "PS1") (pin "3") (pinfunction "+VOUT_3") (pintype "bidirectional"))
    )
    (net (code "80") (name "/W0-1") (class "Default")
      (node (ref "AMP1") (pin "6") (pinfunction "IN2-_6") (pintype "bidirectional"))
      (node (ref "CR1") (pin "1") (pinfunction "W0_1") (pintype "bidirectional"))
      (node (ref "CR1") (pin "2") (pinfunction "B0_2") (pintype "bidirectional"))
      (node (ref "R2_10Ω") (pin "1") (pinfunction "1_1") (pintype "passive"))
    )
    (net (code "81") (name "/W0-2") (class "Default")
      (node (ref "AMP2") (pin "6") (pinfunction "IN2-_6") (pintype "bidirectional"))
      (node (ref "CR2") (pin "1") (pinfunction "W0_1") (pintype "bidirectional"))
      (node (ref "CR2") (pin "2") (pinfunction "B0_2") (pintype "bidirectional"))
      (node (ref "R2_Ω") (pin "1") (pinfunction "1_1") (pintype "passive"))
    )
    (net (code "82") (name "/WP") (class "Default")
      (node (ref "CR1") (pin "5") (pinfunction "~{WP}_5") (pintype "bidirectional"))
      (node (ref "CR2") (pin "5") (pinfunction "~{WP}_5") (pintype "bidirectional"))
      (node (ref "CR3") (pin "5") (pinfunction "~{WP}_5") (pintype "bidirectional"))
      (node (ref "SV1") (pin "19") (pinfunction "19_19") (pintype "passive"))
    )
    (net (code "83") (name "/W_TEST1") (class "Default")
      (node (ref "CR1") (pin "6") (pinfunction "W1_6") (pintype "bidirectional"))
      (node (ref "CR1") (pin "7") (pinfunction "B1_7") (pintype "bidirectional"))
      (node (ref "JP1") (pin "1") (pinfunction "1_1") (pintype "passive"))
    )
    (net (code "84") (name "/W_TEST2") (class "Default")
      (node (ref "CR2") (pin "6") (pinfunction "W1_6") (pintype "bidirectional"))
      (node (ref "CR2") (pin "7") (pinfunction "B1_7") (pintype "bidirectional"))
      (node (ref "JP2") (pin "1") (pinfunction "1_1") (pintype "passive"))
    )
    (net (code "85") (name "/W_TEST3") (class "Default")
      (node (ref "CR3") (pin "12") (pinfunction "B2_12") (pintype "bidirectional"))
      (node (ref "CR3") (pin "13") (pinfunction "W2_13") (pintype "bidirectional"))
      (node (ref "JP3") (pin "1") (pinfunction "1_1") (pintype "passive"))
    )
    (net (code "86") (name "GND") (class "Default")
      (node (ref "ADC1") (pin "1") (pinfunction "ADDR_1") (pintype "bidirectional"))
      (node (ref "ADC1") (pin "2") (pinfunction "ALERT/RDY_2") (pintype "bidirectional"))
      (node (ref "ADC1") (pin "3") (pinfunction "GND_3") (pintype "bidirectional"))
      (node (ref "ADC1") (pin "5") (pinfunction "AIN1_5") (pintype "bidirectional"))
      (node (ref "ADC1") (pin "6") (pinfunction "AIN2_6") (pintype "bidirectional"))
      (node (ref "ADC1") (pin "7") (pinfunction "AIN3_7") (pintype "bidirectional"))
      (node (ref "ADC2") (pin "1") (pinfunction "ADDR_1") (pintype "bidirectional"))
      (node (ref "ADC2") (pin "2") (pinfunction "ALERT/RDY_2") (pintype "bidirectional"))
      (node (ref "ADC2") (pin "3") (pinfunction "GND_3") (pintype "bidirectional"))
      (node (ref "ADC2") (pin "5") (pinfunction "AIN1_5") (pintype "bidirectional"))
      (node (ref "ADC2") (pin "6") (pinfunction "AIN2_6") (pintype "bidirectional"))
      (node (ref "ADC2") (pin "7") (pinfunction "AIN3_7") (pintype "bidirectional"))
      (node (ref "ADC3") (pin "1") (pinfunction "ADDR_1") (pintype "bidirectional"))
      (node (ref "ADC3") (pin "2") (pinfunction "ALERT/RDY_2") (pintype "bidirectional"))
      (node (ref "ADC3") (pin "3") (pinfunction "GND_3") (pintype "bidirectional"))
      (node (ref "ADC3") (pin "5") (pinfunction "AIN1_5") (pintype "bidirectional"))
      (node (ref "ADC3") (pin "6") (pinfunction "AIN2_6") (pintype "bidirectional"))
      (node (ref "ADC3") (pin "7") (pinfunction "AIN3_7") (pintype "bidirectional"))
      (node (ref "AMP1") (pin "4") (pinfunction "V-_4") (pintype "bidirectional"))
      (node (ref "AMP2") (pin "4") (pinfunction "V-_4") (pintype "bidirectional"))
      (node (ref "AMP3") (pin "4") (pinfunction "V-_4") (pintype "bidirectional"))
      (node (ref "CR1") (pin "10") (pinfunction "VSS_10") (pintype "bidirectional"))
      (node (ref "CR1") (pin "11") (pinfunction "A2_11") (pintype "bidirectional"))
      (node (ref "CR1") (pin "12") (pinfunction "B2_12") (pintype "bidirectional"))
      (node (ref "CR1") (pin "13") (pinfunction "W2_13") (pintype "bidirectional"))
      (node (ref "CR1") (pin "15") (pinfunction "DGND_15") (pintype "bidirectional"))
      (node (ref "CR1") (pin "16") (pinfunction "AD1_16") (pintype "bidirectional"))
      (node (ref "CR1") (pin "18") (pinfunction "B3_18") (pintype "bidirectional"))
      (node (ref "CR1") (pin "19") (pinfunction "W3_19") (pintype "bidirectional"))
      (node (ref "CR1") (pin "4") (pinfunction "AD0_4") (pintype "bidirectional"))
      (node (ref "CR2") (pin "10") (pinfunction "VSS_10") (pintype "bidirectional"))
      (node (ref "CR2") (pin "11") (pinfunction "A2_11") (pintype "bidirectional"))
      (node (ref "CR2") (pin "12") (pinfunction "B2_12") (pintype "bidirectional"))
      (node (ref "CR2") (pin "13") (pinfunction "W2_13") (pintype "bidirectional"))
      (node (ref "CR2") (pin "15") (pinfunction "DGND_15") (pintype "bidirectional"))
      (node (ref "CR2") (pin "16") (pinfunction "AD1_16") (pintype "bidirectional"))
      (node (ref "CR2") (pin "18") (pinfunction "B3_18") (pintype "bidirectional"))
      (node (ref "CR2") (pin "19") (pinfunction "W3_19") (pintype "bidirectional"))
      (node (ref "CR2") (pin "4") (pinfunction "AD0_4") (pintype "bidirectional"))
      (node (ref "CR3") (pin "10") (pinfunction "VSS_10") (pintype "bidirectional"))
      (node (ref "CR3") (pin "15") (pinfunction "DGND_15") (pintype "bidirectional"))
      (node (ref "CR3") (pin "16") (pinfunction "AD1_16") (pintype "bidirectional"))
      (node (ref "CR3") (pin "18") (pinfunction "B3_18") (pintype "bidirectional"))
      (node (ref "CR3") (pin "19") (pinfunction "W3_19") (pintype "bidirectional"))
      (node (ref "CR3") (pin "4") (pinfunction "AD0_4") (pintype "bidirectional"))
      (node (ref "CR3") (pin "6") (pinfunction "W1_6") (pintype "bidirectional"))
      (node (ref "CR3") (pin "7") (pinfunction "B1_7") (pintype "bidirectional"))
      (node (ref "CR3") (pin "8") (pinfunction "A1_8") (pintype "bidirectional"))
      (node (ref "C_AD1") (pin "1") (pinfunction "1_1") (pintype "bidirectional"))
      (node (ref "C_AD2") (pin "1") (pinfunction "1_1") (pintype "bidirectional"))
      (node (ref "C_AD3") (pin "1") (pinfunction "1_1") (pintype "bidirectional"))
      (node (ref "C_CR1-1") (pin "1") (pinfunction "1_1") (pintype "bidirectional"))
      (node (ref "C_CR1-2") (pin "1") (pinfunction "1_1") (pintype "bidirectional"))
      (node (ref "C_CR1-3") (pin "1") (pinfunction "1_1") (pintype "bidirectional"))
      (node (ref "C_CR1-4") (pin "1") (pinfunction "1_1") (pintype "bidirectional"))
      (node (ref "C_CR1-5") (pin "1") (pinfunction "1_1") (pintype "bidirectional"))
      (node (ref "C_CR2-1") (pin "1") (pinfunction "1_1") (pintype "bidirectional"))
      (node (ref "C_CR2-2") (pin "1") (pinfunction "1_1") (pintype "bidirectional"))
      (node (ref "C_CR2-3") (pin "1") (pinfunction "1_1") (pintype "bidirectional"))
      (node (ref "C_CR2-4") (pin "1") (pinfunction "1_1") (pintype "bidirectional"))
      (node (ref "C_DA1") (pin "1") (pinfunction "1_1") (pintype "bidirectional"))
      (node (ref "C_DA2") (pin "1") (pinfunction "1_1") (pintype "bidirectional"))
      (node (ref "C_DA3") (pin "1") (pinfunction "1_1") (pintype "bidirectional"))
      (node (ref "C_DA4") (pin "1") (pinfunction "1_1") (pintype "bidirectional"))
      (node (ref "C_DA5") (pin "1") (pinfunction "1_1") (pintype "bidirectional"))
      (node (ref "C_DA6") (pin "1") (pinfunction "1_1") (pintype "bidirectional"))
      (node (ref "C_M1") (pin "1") (pinfunction "1_1") (pintype "bidirectional"))
      (node (ref "C_M2") (pin "1") (pinfunction "1_1") (pintype "bidirectional"))
      (node (ref "C_M3") (pin "1") (pinfunction "1_1") (pintype "bidirectional"))
      (node (ref "DAC1") (pin "2") (pinfunction "VSS_2") (pintype "bidirectional"))
      (node (ref "DAC1") (pin "6") (pinfunction "A0_6") (pintype "bidirectional"))
      (node (ref "DAC2") (pin "2") (pinfunction "VSS_2") (pintype "bidirectional"))
      (node (ref "DAC2") (pin "6") (pinfunction "A0_6") (pintype "bidirectional"))
      (node (ref "DAC3") (pin "2") (pinfunction "VSS_2") (pintype "bidirectional"))
      (node (ref "DAC3") (pin "6") (pinfunction "A0_6") (pintype "bidirectional"))
      (node (ref "J2") (pin "2") (pinfunction "2_2") (pintype "bidirectional"))
      (node (ref "J2") (pin "3") (pinfunction "3_3") (pintype "bidirectional"))
      (node (ref "MP1") (pin "12") (pinfunction "GND_12") (pintype "bidirectional"))
      (node (ref "MP1") (pin "15") (pinfunction "~{E}_15") (pintype "bidirectional"))
      (node (ref "MP2") (pin "12") (pinfunction "GND_12") (pintype "bidirectional"))
      (node (ref "MP2") (pin "15") (pinfunction "~{E}_15") (pintype "bidirectional"))
      (node (ref "MP3") (pin "12") (pinfunction "GND_12") (pintype "bidirectional"))
      (node (ref "MP3") (pin "15") (pinfunction "~{E}_15") (pintype "bidirectional"))
      (node (ref "PS1") (pin "2") (pinfunction "GND_2") (pintype "bidirectional"))
      (node (ref "SV1") (pin "9") (pinfunction "9_9") (pintype "passive"))
      (node (ref "SV6") (pin "13") (pinfunction "13_13") (pintype "passive"))
    )
    (net (code "87") (name "Net-(AMP3-IN2+)") (class "Default")
      (node (ref "AMP3") (pin "5") (pinfunction "IN2+_5") (pintype "bidirectional"))
      (node (ref "CR3") (pin "17") (pinfunction "A3_17") (pintype "bidirectional"))
      (node (ref "R3-4") (pin "1") (pinfunction "1_1") (pintype "passive"))
    )
    (net (code "88") (name "Net-(AMP3-IN2-)") (class "Default")
      (node (ref "AMP3") (pin "6") (pinfunction "IN2-_6") (pintype "bidirectional"))
      (node (ref "CR3") (pin "1") (pinfunction "W0_1") (pintype "bidirectional"))
      (node (ref "CR3") (pin "2") (pinfunction "B0_2") (pintype "bidirectional"))
      (node (ref "R3-2") (pin "1") (pinfunction "1_1") (pintype "passive"))
    )
    (net (code "89") (name "unconnected-(SV1-Pad1)") (class "Default")
      (node (ref "SV1") (pin "1") (pinfunction "1_1") (pintype "passive"))
    )
    (net (code "90") (name "unconnected-(SV1-Pad4)") (class "Default")
      (node (ref "SV1") (pin "4") (pinfunction "4_4") (pintype "passive"))
    )
    (net (code "91") (name "unconnected-(SV1-Pad6)") (class "Default")
      (node (ref "SV1") (pin "6") (pinfunction "6_6") (pintype "passive"))
    )
    (net (code "92") (name "unconnected-(SV1-Pad7)") (class "Default")
      (node (ref "SV1") (pin "7") (pinfunction "7_7") (pintype "passive"))
    )
    (net (code "93") (name "unconnected-(SV1-Pad8)") (class "Default")
      (node (ref "SV1") (pin "8") (pinfunction "8_8") (pintype "passive"))
    )
    (net (code "94") (name "unconnected-(SV1-Pad10)") (class "Default")
      (node (ref "SV1") (pin "10") (pinfunction "10_10") (pintype "passive"))
    )
    (net (code "95") (name "unconnected-(SV1-Pad12)") (class "Default")
      (node (ref "SV1") (pin "12") (pinfunction "12_12") (pintype "passive"))
    )
    (net (code "96") (name "unconnected-(SV1-Pad14)") (class "Default")
      (node (ref "SV1") (pin "14") (pinfunction "14_14") (pintype "passive"))
    )
    (net (code "97") (name "unconnected-(SV1-Pad18)") (class "Default")
      (node (ref "SV1") (pin "18") (pinfunction "18_18") (pintype "passive"))
    )
    (net (code "98") (name "unconnected-(SV1-Pad20)") (class "Default")
      (node (ref "SV1") (pin "20") (pinfunction "20_20") (pintype "passive"))
    )
    (net (code "99") (name "unconnected-(SV1-Pad22)") (class "Default")
      (node (ref "SV1") (pin "22") (pinfunction "22_22") (pintype "passive"))
    )
    (net (code "100") (name "unconnected-(SV1-Pad23)") (class "Default")
      (node (ref "SV1") (pin "23") (pinfunction "23_23") (pintype "passive"))
    )
    (net (code "101") (name "unconnected-(SV1-Pad25)") (class "Default")
      (node (ref "SV1") (pin "25") (pinfunction "25_25") (pintype "passive"))
    )
    (net (code "102") (name "unconnected-(SV1-Pad26)") (class "Default")
      (node (ref "SV1") (pin "26") (pinfunction "26_26") (pintype "passive"))
    )
    (net (code "103") (name "unconnected-(SV1-Pad27)") (class "Default")
      (node (ref "SV1") (pin "27") (pinfunction "27_27") (pintype "passive"))
    )
    (net (code "104") (name "unconnected-(SV1-Pad28)") (class "Default")
      (node (ref "SV1") (pin "28") (pinfunction "28_28") (pintype "passive"))
    )
    (net (code "105") (name "unconnected-(SV1-Pad29)") (class "Default")
      (node (ref "SV1") (pin "29") (pinfunction "29_29") (pintype "passive"))
    )
    (net (code "106") (name "unconnected-(SV1-Pad30)") (class "Default")
      (node (ref "SV1") (pin "30") (pinfunction "30_30") (pintype "passive"))
    )
    (net (code "107") (name "unconnected-(SV1-Pad31)") (class "Default")
      (node (ref "SV1") (pin "31") (pinfunction "31_31") (pintype "passive"))
    )
    (net (code "108") (name "unconnected-(SV1-Pad34)") (class "Default")
      (node (ref "SV1") (pin "34") (pinfunction "34_34") (pintype "passive"))
    )
    (net (code "109") (name "unconnected-(SV1-Pad35)") (class "Default")
      (node (ref "SV1") (pin "35") (pinfunction "35_35") (pintype "passive"))
    )
    (net (code "110") (name "unconnected-(SV1-Pad36)") (class "Default")
      (node (ref "SV1") (pin "36") (pinfunction "36_36") (pintype "passive"))
    )
    (net (code "111") (name "unconnected-(SV1-Pad37)") (class "Default")
      (node (ref "SV1") (pin "37") (pinfunction "37_37") (pintype "passive"))
    )
    (net (code "112") (name "unconnected-(SV1-Pad38)") (class "Default")
      (node (ref "SV1") (pin "38") (pinfunction "38_38") (pintype "passive"))
    )
    (net (code "113") (name "unconnected-(SV1-Pad39)") (class "Default")
      (node (ref "SV1") (pin "39") (pinfunction "39_39") (pintype "passive"))
    )
    (net (code "114") (name "unconnected-(SV1-Pad40)") (class "Default")
      (node (ref "SV1") (pin "40") (pinfunction "40_40") (pintype "passive"))
    )
  )
)
